# 03_POWER.net
KiCad netlist of a schematic drawn in Altium Designer
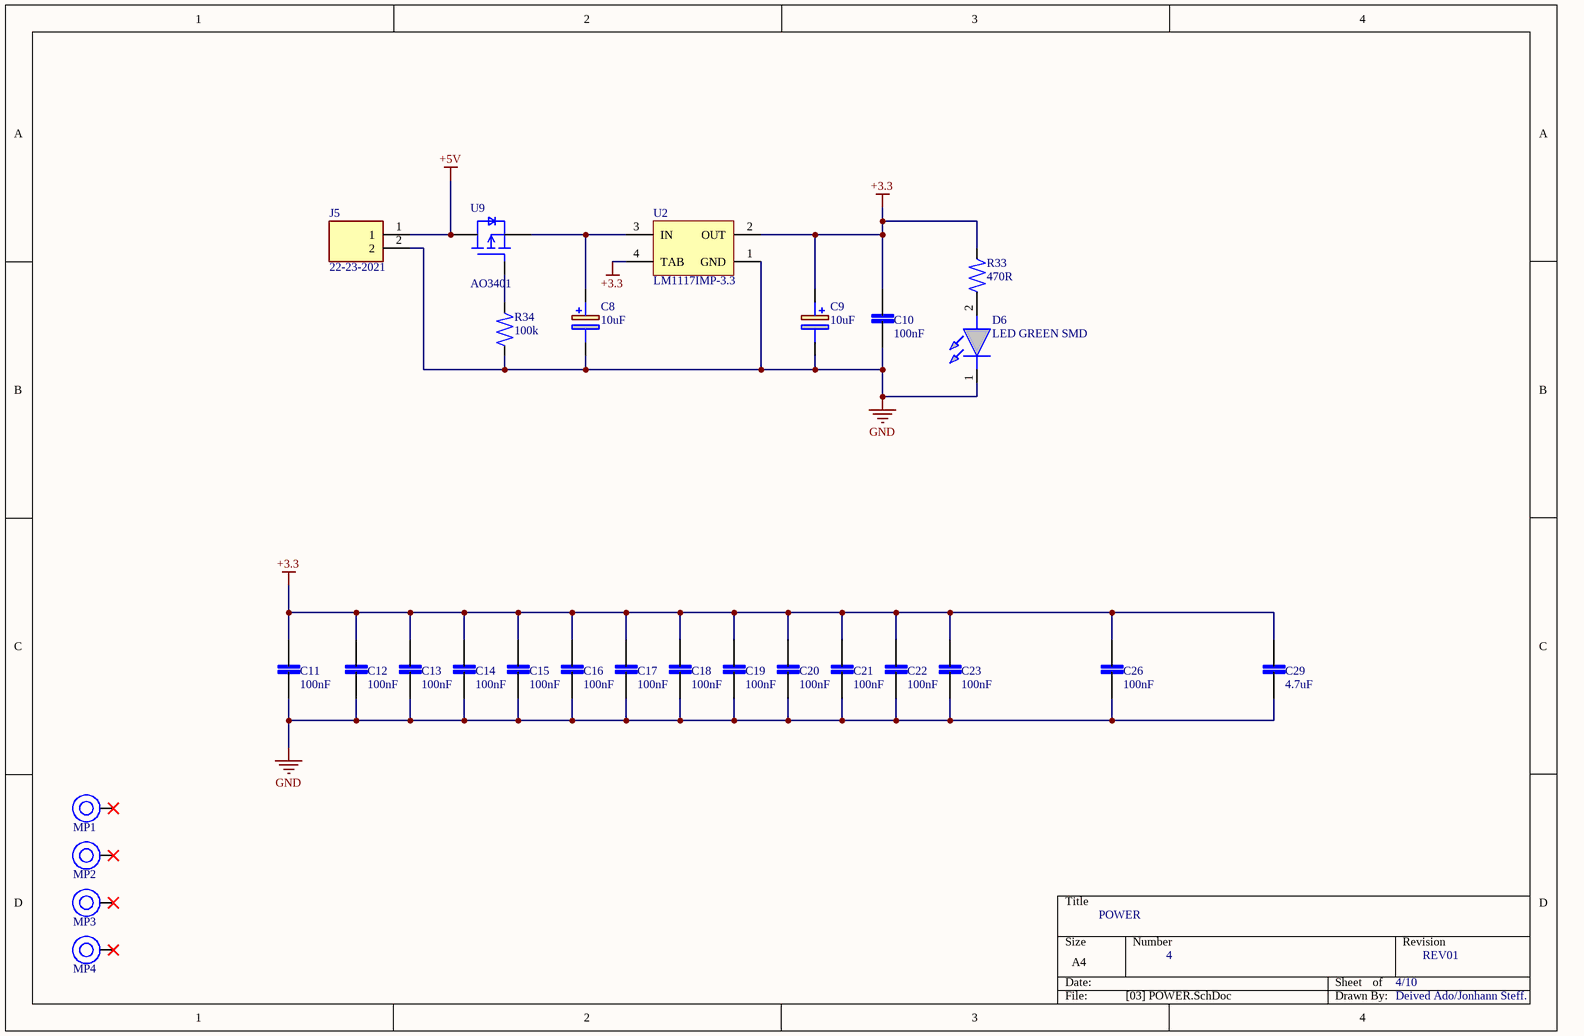
[diagram p0: [03] POWER.SchDoc]

(export (version "E")
  (design (tool "Eeschema 10.0.6"))
  (components
    (comp (ref "C8")
      (value "10uF")
      (footprint "CAP_E_830X650N")
      (libsource (lib "Integrated_Library - Rev1") (part "C_CP"))
    )
    (comp (ref "C9") (value "10uF") (footprint "CAP_E_830X650N") (libsource (lib "") (part "C_CP_1")))
    (comp (ref "C10")
      (value "100nF")
      (footprint "cap_0603")
      (description "Generic capacitor symbol")
      (libsource (lib "Integrated_Library - Rev1") (part "C_Small"))
    )
    (comp (ref "C11")
      (value "100nF")
      (footprint "cap_0603")
      (description "Generic capacitor symbol")
      (libsource (lib "Integrated_Library - Rev1") (part "C_Small"))
    )
    (comp (ref "C12")
      (value "100nF")
      (footprint "cap_0603")
      (description "Generic capacitor symbol")
      (libsource (lib "Integrated_Library - Rev1") (part "C_Small"))
    )
    (comp (ref "C13")
      (value "100nF")
      (footprint "cap_0603")
      (description "Generic capacitor symbol")
      (libsource (lib "Integrated_Library - Rev1") (part "C_Small"))
    )
    (comp (ref "C14")
      (value "100nF")
      (footprint "cap_0603")
      (description "Generic capacitor symbol")
      (libsource (lib "Integrated_Library - Rev1") (part "C_Small"))
    )
    (comp (ref "C15")
      (value "100nF")
      (footprint "cap_0603")
      (description "Generic capacitor symbol")
      (libsource (lib "Integrated_Library - Rev1") (part "C_Small"))
    )
    (comp (ref "C16")
      (value "100nF")
      (footprint "cap_0603")
      (description "Generic capacitor symbol")
      (libsource (lib "Integrated_Library - Rev1") (part "C_Small"))
    )
    (comp (ref "C17")
      (value "100nF")
      (footprint "cap_0603")
      (description "Generic capacitor symbol")
      (libsource (lib "Integrated_Library - Rev1") (part "C_Small"))
    )
    (comp (ref "C18")
      (value "100nF")
      (footprint "cap_0603")
      (description "Generic capacitor symbol")
      (libsource (lib "Integrated_Library - Rev1") (part "C_Small"))
    )
    (comp (ref "C19")
      (value "100nF")
      (footprint "cap_0603")
      (description "Generic capacitor symbol")
      (libsource (lib "Integrated_Library - Rev1") (part "C_Small"))
    )
    (comp (ref "C20")
      (value "100nF")
      (footprint "cap_0603")
      (description "Generic capacitor symbol")
      (libsource (lib "Integrated_Library - Rev1") (part "C_Small"))
    )
    (comp (ref "C21")
      (value "100nF")
      (footprint "cap_0603")
      (description "Generic capacitor symbol")
      (libsource (lib "Integrated_Library - Rev1") (part "C_Small"))
    )
    (comp (ref "C22")
      (value "100nF")
      (footprint "cap_0603")
      (description "Generic capacitor symbol")
      (libsource (lib "Integrated_Library - Rev1") (part "C_Small"))
    )
    (comp (ref "C23")
      (value "100nF")
      (footprint "cap_0603")
      (description "Generic capacitor symbol")
      (libsource (lib "Integrated_Library - Rev1") (part "C_Small"))
    )
    (comp (ref "C26")
      (value "100nF")
      (footprint "cap_0603")
      (description "Generic capacitor symbol")
      (libsource (lib "Integrated_Library - Rev1") (part "C_Small"))
    )
    (comp (ref "C29")
      (value "4.7uF")
      (footprint "cap_0603")
      (description "Generic capacitor symbol")
      (libsource (lib "Integrated_Library - Rev1") (part "C_Small"))
    )
    (comp (ref "D6")
      (value "LED GREEN SMD")
      (footprint "LED 0805")
      (description "LED Green 0805 Rectangular")
      (fields (field (name "MFR. PART #") "15008GS75000") (field (name "MANUFACTURER") "Wurth Elektronik"))
      (libsource (lib "Integrated_Library_IST") (part "LED GREEN SMD"))
    )
    (comp (ref "J5")
      (value "22-23-2021")
      (footprint "SHDR2W87P0X254_1X2_493X635X1105P")
      (description "Headers & Wire Housings VERT PCB HDR 2P TIN FRICTION LOCK")
      (fields (field (name "MANUFACTURER") "Molex"))
      (libsource (lib "Integrated_Library_IST") (part "KK - HDR 2P"))
    )
    (comp (ref "MP1")
      (value "M3 x 5mm")
      (footprint "78614050360")
      (description "WA-SMSA SMT Spacer Studs Automotive, OD 6mm, ID 4.2mm, M3 x 5mm")
      (fields
        (field (name "MANUFACTURER PART NUMBER") "78614050360")
        (field (name "MANUFACTURER") "Wurth Elektronik")
      )
      (libsource (lib "WE - Electromechanical Components") (part "Spacer"))
    )
    (comp (ref "MP2")
      (value "M3 x 5mm")
      (footprint "78614050360")
      (description "WA-SMSA SMT Spacer Studs Automotive, OD 6mm, ID 4.2mm, M3 x 5mm")
      (fields
        (field (name "MANUFACTURER PART NUMBER") "78614050360")
        (field (name "MANUFACTURER") "Wurth Elektronik")
      )
      (libsource (lib "WE - Electromechanical Components") (part "Spacer"))
    )
    (comp (ref "MP3")
      (value "M3 x 5mm")
      (footprint "78614050360")
      (description "WA-SMSA SMT Spacer Studs Automotive, OD 6mm, ID 4.2mm, M3 x 5mm")
      (fields
        (field (name "MANUFACTURER PART NUMBER") "78614050360")
        (field (name "MANUFACTURER") "Wurth Elektronik")
      )
      (libsource (lib "WE - Electromechanical Components") (part "Spacer"))
    )
    (comp (ref "MP4")
      (value "M3 x 5mm")
      (footprint "78614050360")
      (description "WA-SMSA SMT Spacer Studs Automotive, OD 6mm, ID 4.2mm, M3 x 5mm")
      (fields
        (field (name "MANUFACTURER PART NUMBER") "78614050360")
        (field (name "MANUFACTURER") "Wurth Elektronik")
      )
      (libsource (lib "WE - Electromechanical Components") (part "Spacer"))
    )
    (comp (ref "R33")
      (value "470R")
      (footprint "RES_0603")
      (description "Generic Resistor symbol")
      (libsource (lib "Integrated_Library_IST") (part "R_Small"))
    )
    (comp (ref "R34")
      (value "100k")
      (footprint "RES_0603")
      (description "Generic Resistor symbol")
      (libsource (lib "Integrated_Library_IST") (part "R_Small"))
    )
    (comp (ref "U2")
      (value "LM1117IMP-3.3")
      (footprint "MP04A_N")
      (description "800mA Low-Dropout Linear Regulator, 4-pin SOT-223")
      (fields
        (field (name "MANUFACTURER") "National Semiconductor")
        (field (name "PUBLISHER") "Altium Limited")
      )
      (libsource (lib "NSC LDO") (part "LM1117IMP-3.3"))
    )
    (comp (ref "U9")
      (value "AO3401")
      (footprint "SOT23-3")
      (description "P-Channel 30 V 4A (Ta) 1.4W (Ta) Surface Mount SOT-23-3")
      (fields (field (name "MF") "Alpha &"))
      (libsource (lib "Integrated_Library_IST") (part "AO3401"))
    )
  )
  (nets
    (net (code "1") (name "+3.3") (class "Default")
      (node (ref "C10") (pin "2") (pinfunction "2_2") (pintype "passive"))
      (node (ref "C11") (pin "2") (pinfunction "2_2") (pintype "passive"))
      (node (ref "C12") (pin "2") (pinfunction "2_2") (pintype "passive"))
      (node (ref "C13") (pin "2") (pinfunction "2_2") (pintype "passive"))
      (node (ref "C14") (pin "2") (pinfunction "2_2") (pintype "passive"))
      (node (ref "C15") (pin "2") (pinfunction "2_2") (pintype "passive"))
      (node (ref "C16") (pin "2") (pinfunction "2_2") (pintype "passive"))
      (node (ref "C17") (pin "2") (pinfunction "2_2") (pintype "passive"))
      (node (ref "C18") (pin "2") (pinfunction "2_2") (pintype "passive"))
      (node (ref "C19") (pin "2") (pinfunction "2_2") (pintype "passive"))
      (node (ref "C20") (pin "2") (pinfunction "2_2") (pintype "passive"))
      (node (ref "C21") (pin "2") (pinfunction "2_2") (pintype "passive"))
      (node (ref "C22") (pin "2") (pinfunction "2_2") (pintype "passive"))
      (node (ref "C23") (pin "2") (pinfunction "2_2") (pintype "passive"))
      (node (ref "C26") (pin "2") (pinfunction "2_2") (pintype "passive"))
      (node (ref "C29") (pin "2") (pinfunction "2_2") (pintype "passive"))
      (node (ref "C9") (pin "1") (pinfunction "+_1") (pintype "passive"))
      (node (ref "R33") (pin "2") (pinfunction "2_2") (pintype "passive"))
      (node (ref "U2") (pin "2") (pinfunction "OUT_2") (pintype "power_in"))
      (node (ref "U2") (pin "4") (pinfunction "TAB_4") (pintype "power_in"))
    )
    (net (code "2") (name "+5V") (class "Default")
      (node (ref "J5") (pin "1") (pinfunction "1_1") (pintype "passive"))
      (node (ref "U9") (pin "3") (pinfunction "D_3") (pintype "passive"))
    )
    (net (code "3") (name "GND") (class "Default")
      (node (ref "C10") (pin "1") (pinfunction "1_1") (pintype "passive"))
      (node (ref "C11") (pin "1") (pinfunction "1_1") (pintype "passive"))
      (node (ref "C12") (pin "1") (pinfunction "1_1") (pintype "passive"))
      (node (ref "C13") (pin "1") (pinfunction "1_1") (pintype "passive"))
      (node (ref "C14") (pin "1") (pinfunction "1_1") (pintype "passive"))
      (node (ref "C15") (pin "1") (pinfunction "1_1") (pintype "passive"))
      (node (ref "C16") (pin "1") (pinfunction "1_1") (pintype "passive"))
      (node (ref "C17") (pin "1") (pinfunction "1_1") (pintype "passive"))
      (node (ref "C18") (pin "1") (pinfunction "1_1") (pintype "passive"))
      (node (ref "C19") (pin "1") (pinfunction "1_1") (pintype "passive"))
      (node (ref "C20") (pin "1") (pinfunction "1_1") (pintype "passive"))
      (node (ref "C21") (pin "1") (pinfunction "1_1") (pintype "passive"))
      (node (ref "C22") (pin "1") (pinfunction "1_1") (pintype "passive"))
      (node (ref "C23") (pin "1") (pinfunction "1_1") (pintype "passive"))
      (node (ref "C26") (pin "1") (pinfunction "1_1") (pintype "passive"))
      (node (ref "C29") (pin "1") (pinfunction "1_1") (pintype "passive"))
      (node (ref "C8") (pin "2") (pinfunction "-_2") (pintype "passive"))
      (node (ref "C9") (pin "2") (pinfunction "-_2") (pintype "passive"))
      (node (ref "D6") (pin "1") (pinfunction "K_1") (pintype "passive"))
      (node (ref "J5") (pin "2") (pinfunction "2_2") (pintype "passive"))
      (node (ref "R34") (pin "1") (pinfunction "1_1") (pintype "passive"))
      (node (ref "U2") (pin "1") (pinfunction "GND_1") (pintype "power_in"))
    )
    (net (code "4") (name "Net-(C8-+)") (class "Default")
      (node (ref "C8") (pin "1") (pinfunction "+_1") (pintype "passive"))
      (node (ref "U2") (pin "3") (pinfunction "IN_3") (pintype "power_in"))
      (node (ref "U9") (pin "2") (pinfunction "S_2") (pintype "passive"))
    )
    (net (code "5") (name "Net-(D6-A)") (class "Default")
      (node (ref "D6") (pin "2") (pinfunction "A_2") (pintype "passive"))
      (node (ref "R33") (pin "1") (pinfunction "1_1") (pintype "passive"))
    )
    (net (code "6") (name "Net-(U9-G)") (class "Default")
      (node (ref "R34") (pin "2") (pinfunction "2_2") (pintype "passive"))
      (node (ref "U9") (pin "1") (pinfunction "G_1") (pintype "passive"))
    )
    (net (code "7") (name "unconnected-(MP1-Pad1)") (class "Default")
      (node (ref "MP1") (pin "1") (pinfunction "1_1") (pintype "passive+no_connect"))
    )
    (net (code "8") (name "unconnected-(MP2-Pad1)") (class "Default")
      (node (ref "MP2") (pin "1") (pinfunction "1_1") (pintype "passive+no_connect"))
    )
    (net (code "9") (name "unconnected-(MP3-Pad1)") (class "Default")
      (node (ref "MP3") (pin "1") (pinfunction "1_1") (pintype "passive+no_connect"))
    )
    (net (code "10") (name "unconnected-(MP4-Pad1)") (class "Default")
      (node (ref "MP4") (pin "1") (pinfunction "1_1") (pintype "passive+no_connect"))
    )
  )
)
